# ProDoc.net
KiCad netlist of a schematic drawn in EasyEDA Pro
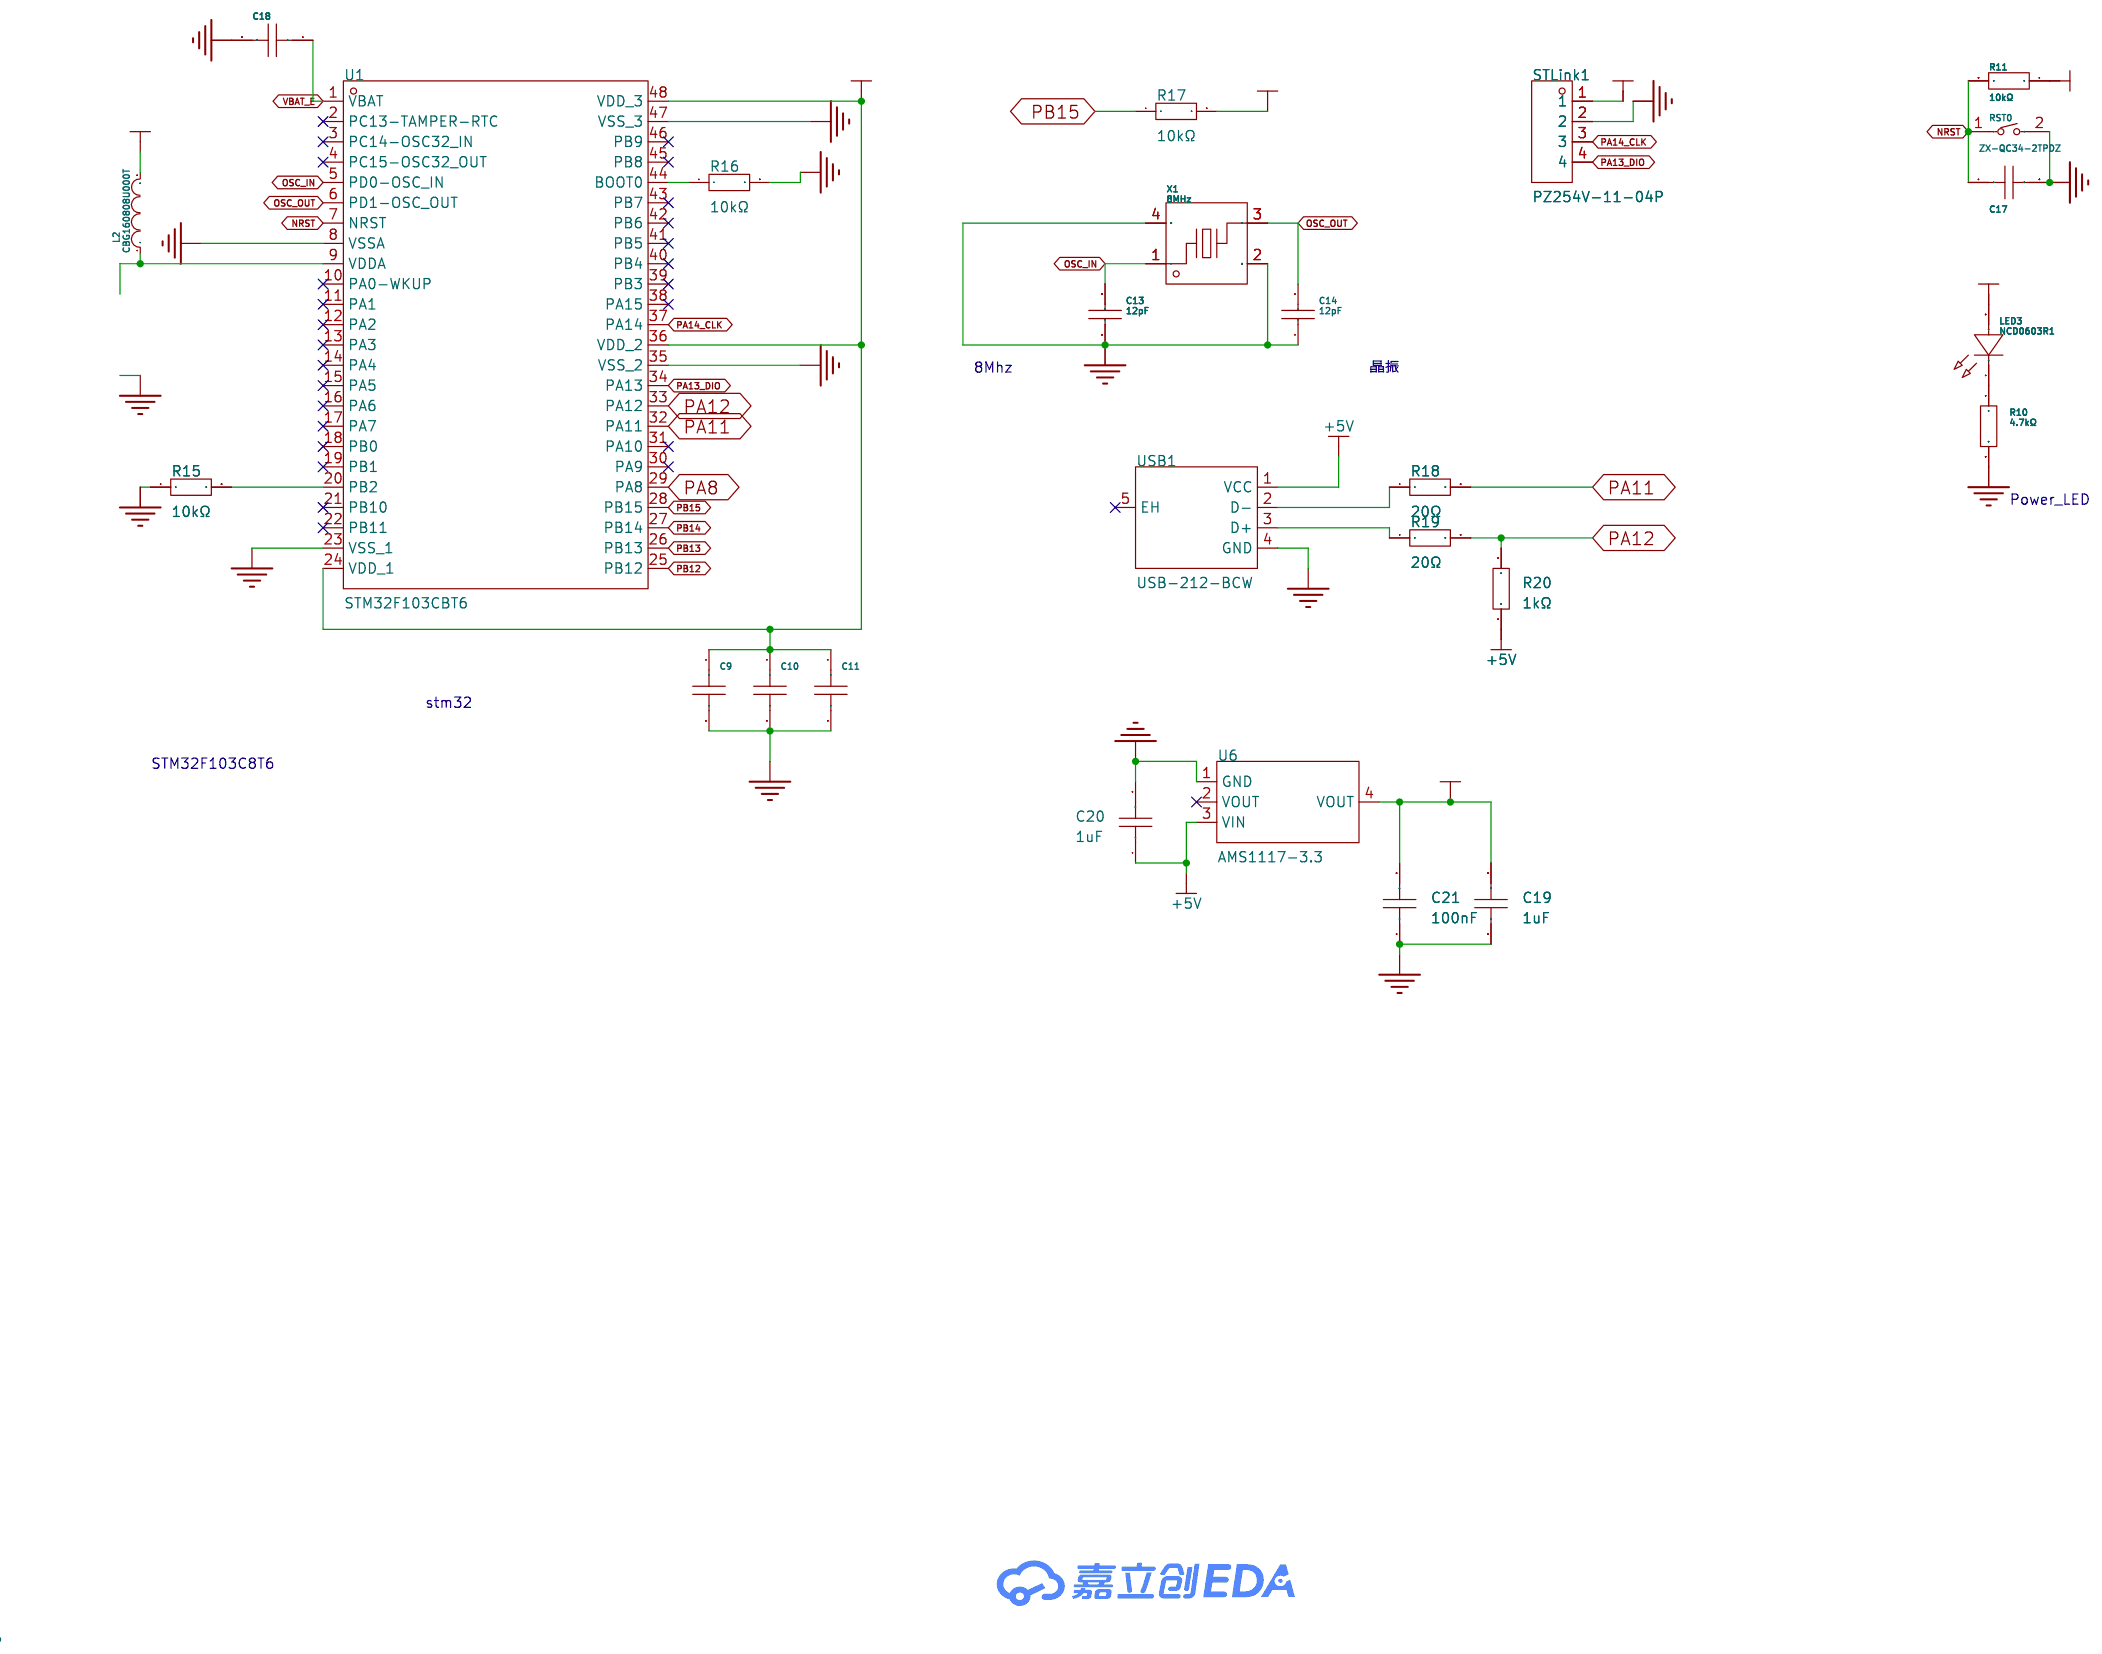
[diagram p0: P1]
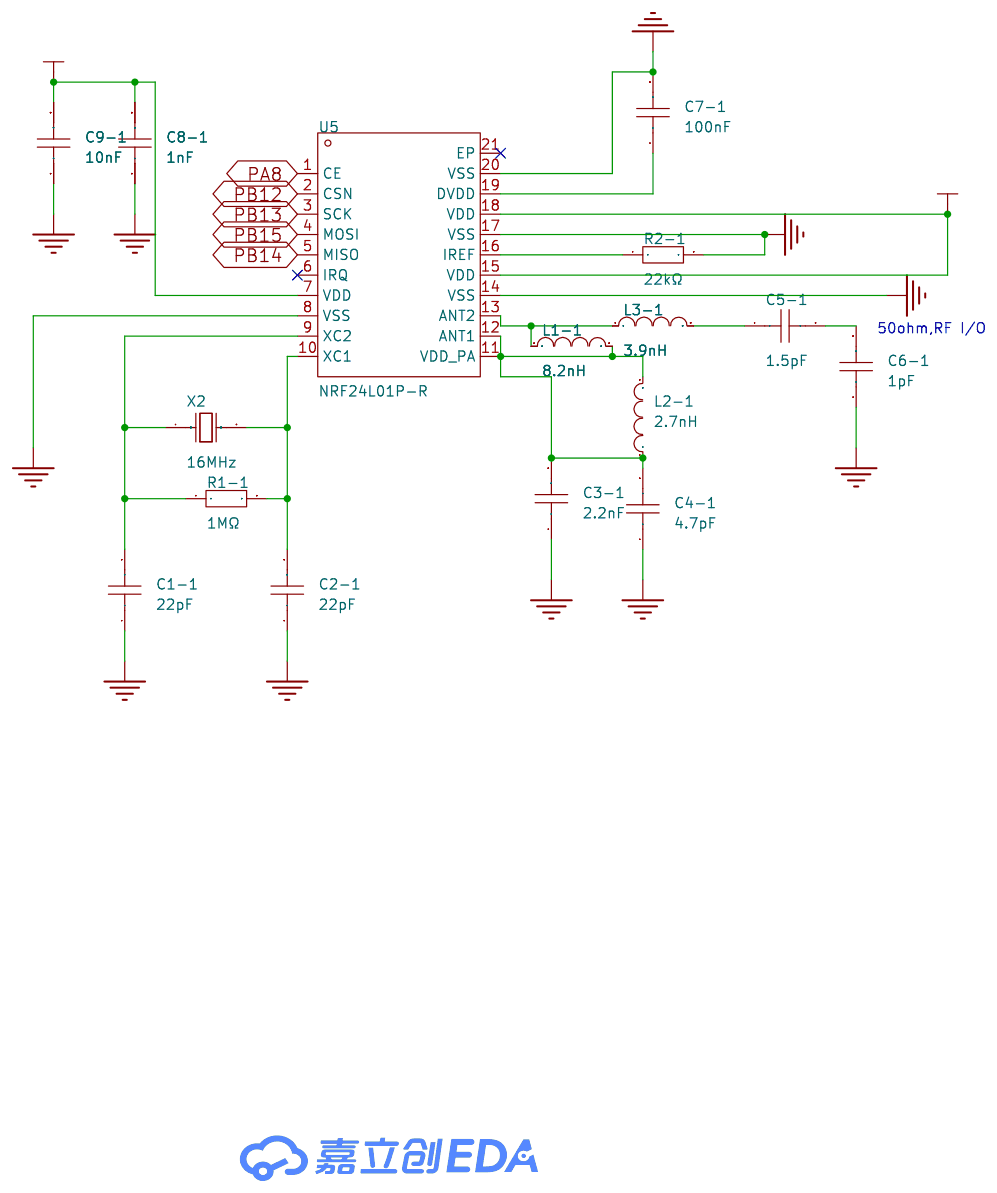
[diagram p1: P2]

(export (version "E")
  (design (tool "Eeschema 10.0.6"))
  (components
    (comp (ref "C9")
      (value "100nF")
      (fields
        (field (name "Manufacturer Part") "CT41G-0603-2X1-50V-0.1μF-K(N)")
        (field (name "Manufacturer") "TORCH(火炬)")
      )
      (libsource (lib "easyedapro") (part "CC0603JRNPO9BN101"))
    )
    (comp (ref "C10")
      (value "100nF")
      (fields
        (field (name "Manufacturer Part") "CT41G-0603-2X1-50V-0.1μF-K(N)")
        (field (name "Manufacturer") "TORCH(火炬)")
      )
      (libsource (lib "easyedapro") (part "CC0603JRNPO9BN101"))
    )
    (comp (ref "C11")
      (value "100nF")
      (fields
        (field (name "Manufacturer Part") "CT41G-0603-2X1-50V-0.1μF-K(N)")
        (field (name "Manufacturer") "TORCH(火炬)")
      )
      (libsource (lib "easyedapro") (part "CC0603JRNPO9BN101"))
    )
    (comp (ref "C13")
      (value "12pF")
      (fields
        (field (name "Manufacturer Part") "CL10C120JB8NNNC")
        (field (name "Manufacturer") "SAMSUNG(三星)")
      )
      (libsource (lib "easyedapro") (part "CC0603JRNPO9BN200"))
    )
    (comp (ref "C14")
      (value "12pF")
      (fields
        (field (name "Manufacturer Part") "CL10C120JB8NNNC")
        (field (name "Manufacturer") "SAMSUNG(三星)")
      )
      (libsource (lib "easyedapro") (part "CC0603JRNPO9BN200"))
    )
    (comp (ref "C17")
      (value "100nF")
      (fields
        (field (name "Manufacturer Part") "CT41G-0603-2X1-50V-0.1μF-K(N)")
        (field (name "Manufacturer") "TORCH(火炬)")
      )
      (libsource (lib "easyedapro") (part "CC0603JRNPO9BN101"))
    )
    (comp (ref "C18")
      (value "100nF")
      (fields
        (field (name "Manufacturer Part") "CT41G-0603-2X1-50V-0.1μF-K(N)")
        (field (name "Manufacturer") "TORCH(火炬)")
      )
      (libsource (lib "easyedapro") (part "CC0603JRNPO9BN101"))
    )
    (comp (ref "C19")
      (value "1uF")
      (footprint "easyedapro:C0603")
      (description "容值:1uF;精度:±10%;额定电压:50V;温度系数:X5R;")
      (fields
        (field (name "Manufacturer Part") "CL10A105KB8NNNC")
        (field (name "Manufacturer") "SAMSUNG(三星)")
      )
      (libsource (lib "easyedapro") (part "CL10A105KB8NNNC"))
    )
    (comp (ref "C20")
      (value "1uF")
      (footprint "easyedapro:C0603")
      (description "容值:1uF;精度:±10%;额定电压:50V;温度系数:X5R;")
      (fields
        (field (name "Manufacturer Part") "CL10A105KB8NNNC")
        (field (name "Manufacturer") "SAMSUNG(三星)")
      )
      (libsource (lib "easyedapro") (part "CL10A105KB8NNNC"))
    )
    (comp (ref "C21")
      (value "100nF")
      (footprint "easyedapro:C0603")
      (description "容值:100nF;精度:±10%;额定电压:50V;温度系数:X7R;")
      (fields
        (field (name "Manufacturer Part") "CGA0603X7R104K500JT")
        (field (name "Manufacturer") "HRE(芯声)")
      )
      (libsource (lib "easyedapro") (part "CGA0603X7R104K500JT"))
    )
    (comp (ref "L2")
      (value "CBG160808U000T")
      (footprint "easyedapro:L0603")
      (description "标称阻抗@测试频率:0Ω@100MHz;直流电阻(RDC):100mΩ;")
      (fields (field (name "Manufacturer") "FH(风华)"))
      (libsource (lib "easyedapro") (part "CBG160808U000T"))
    )
    (comp (ref "LED3")
      (value "NCD0603R1")
      (fields (field (name "Manufacturer") "国星光电"))
      (libsource (lib "easyedapro") (part "XL-1608SURC-06"))
    )
    (comp (ref "R10")
      (value "4.7kΩ")
      (footprint "easyedapro:R0603")
      (description "电阻类型:厚膜电阻;阻值:10kΩ;精度:±1%;功率:100mW;最大工作电压:75V;温度系数:±100ppm/°C;")
      (fields
        (field (name "Manufacturer Part") "0603WAF4701T5E")
        (field (name "Manufacturer") "UNI-ROYAL(厚声)")
      )
      (libsource (lib "easyedapro") (part "0603WAF1002T5E"))
    )
    (comp (ref "R11")
      (value "10kΩ")
      (footprint "easyedapro:R0603")
      (description "电阻类型:厚膜电阻;阻值:10kΩ;精度:±1%;功率:100mW;工作电压:75V;温度系数:±100ppm/℃;")
      (fields
        (field (name "Manufacturer Part") "0603WAF1002T5E")
        (field (name "Manufacturer") "UNI-ROYAL(厚声)")
      )
      (libsource (lib "easyedapro") (part "0603WAF1002T5E"))
    )
    (comp (ref "R15")
      (value "10kΩ")
      (description "电阻类型:厚膜电阻;阻值:10kΩ;精度:±1%;功率:100mW;工作电压:75V;温度系数:±100ppm/℃;")
      (fields
        (field (name "Manufacturer Part") "0603WAF1002T5E")
        (field (name "Manufacturer") "UNI-ROYAL(厚声)")
      )
      (libsource (lib "easyedapro") (part "电阻"))
    )
    (comp (ref "R16")
      (value "10kΩ")
      (description "电阻类型:厚膜电阻;阻值:10kΩ;精度:±1%;功率:100mW;工作电压:75V;温度系数:±100ppm/℃;")
      (fields
        (field (name "Manufacturer Part") "0603WAF1002T5E")
        (field (name "Manufacturer") "UNI-ROYAL(厚声)")
      )
      (libsource (lib "easyedapro") (part "电阻"))
    )
    (comp (ref "R17")
      (value "10kΩ")
      (description "电阻类型:厚膜电阻;阻值:10kΩ;精度:±1%;功率:100mW;工作电压:75V;温度系数:±100ppm/℃;")
      (fields
        (field (name "Manufacturer Part") "0603WAF1002T5E")
        (field (name "Manufacturer") "UNI-ROYAL(厚声)")
      )
      (libsource (lib "easyedapro") (part "电阻"))
    )
    (comp (ref "R18")
      (value "20Ω")
      (footprint "easyedapro:R0603")
      (description "电阻类型:厚膜电阻;阻值:20Ω;精度:±1%;功率:100mW;最大工作电压:75V;温度系数:±100ppm/°C;")
      (fields
        (field (name "Manufacturer Part") "0603WAF200JT5E")
        (field (name "Manufacturer") "UNI-ROYAL(厚声)")
      )
      (libsource (lib "easyedapro") (part "0603WAF200JT5E"))
    )
    (comp (ref "R19")
      (value "20Ω")
      (footprint "easyedapro:R0603")
      (description "电阻类型:厚膜电阻;阻值:20Ω;精度:±1%;功率:100mW;最大工作电压:75V;温度系数:±100ppm/°C;")
      (fields
        (field (name "Manufacturer Part") "0603WAF200JT5E")
        (field (name "Manufacturer") "UNI-ROYAL(厚声)")
      )
      (libsource (lib "easyedapro") (part "0603WAF200JT5E"))
    )
    (comp (ref "R20")
      (value "1kΩ")
      (footprint "easyedapro:R0603")
      (description "电阻类型:厚膜电阻;阻值:1kΩ;精度:±1%;功率:100mW;最大工作电压:75V;温度系数:±100ppm/°C;")
      (fields
        (field (name "Manufacturer Part") "0603WAF1001T5E")
        (field (name "Manufacturer") "UNI-ROYAL(厚声)")
      )
      (libsource (lib "easyedapro") (part "0603WAF1001T5E"))
    )
    (comp (ref "RST0")
      (value "ZX-QC34-2TPDZ")
      (footprint "easyedapro:KEY-SMD_L3.9-W3.0-LS5.0-EH")
      (fields (field (name "Manufacturer") "Megastar(兆星)"))
      (libsource (lib "easyedapro") (part "ZX-QC34-2TPDZ"))
    )
    (comp (ref "STLink1")
      (value "PZ254V-11-04P")
      (footprint "easyedapro:HDR-TH_4P-P2.54-V-M")
      (fields (field (name "Manufacturer") "XFCN(兴飞)"))
      (libsource (lib "easyedapro") (part "PZ254V-11-04P_C2691448"))
    )
    (comp (ref "U1")
      (value "STM32F103CBT6")
      (fields (field (name "Manufacturer") "ST(意法半导体)"))
      (libsource (lib "easyedapro") (part "APM32F103CBT6"))
    )
    (comp (ref "U6")
      (value "AMS1117-3.3")
      (footprint "easyedapro:SOT-223-3_L6.5-W3.4-P2.30-LS7.0-BR")
      (description "输出类型:固定;工作电压:16V;输出电压:3.3V;输出电流:1A;电源纹波抑制比(PSRR):72dB@(120Hz);输出极性:正极;")
      (fields (field (name "Manufacturer") "AMS"))
      (libsource (lib "easyedapro") (part "AMS1117-3.3"))
    )
    (comp (ref "USB1")
      (value "USB-212-BCW")
      (footprint "easyedapro:USB-A-SMD_USB-212-BCW")
      (description "连接器类型:Type-A;协议标准:USB 2.0;公母:公;安装方式:卧贴;触点数量:4P;端口数量:1;额定电流 - 电源:1.5A;工作温度:-20°C~+70°C;")
      (fields (field (name "Manufacturer") "XUNPU(讯普)"))
      (libsource (lib "easyedapro") (part "USB-212-BCW"))
    )
    (comp (ref "X1")
      (value "8MHz")
      (fields (field (name "Manufacturer Part") "X32258MOB4SI") (field (name "Manufacturer") "YXC(扬兴晶振)"))
      (libsource (lib "easyedapro") (part "X32258MOB4SI"))
    )
    (comp (ref "C1-1")
      (value "22pF")
      (fields
        (field (name "Manufacturer Part") "CL10C220JB8NNNC")
        (field (name "Manufacturer") "SAMSUNG(三星)")
      )
      (libsource (lib "easyedapro") (part "Capacitance"))
    )
    (comp (ref "C2-1")
      (value "22pF")
      (fields
        (field (name "Manufacturer Part") "CL10C220JB8NNNC")
        (field (name "Manufacturer") "SAMSUNG(三星)")
      )
      (libsource (lib "easyedapro") (part "Capacitance"))
    )
    (comp (ref "C3-1")
      (value "2.2nF")
      (fields
        (field (name "Manufacturer Part") "FCC0603B222K500CT")
        (field (name "Manufacturer") "FOJAN(富捷)")
      )
      (libsource (lib "easyedapro") (part "Capacitance"))
    )
    (comp (ref "C4-1")
      (value "4.7pF")
      (fields (field (name "Manufacturer Part") "0603CG4R7C500NT") (field (name "Manufacturer") "FH(风华)"))
      (libsource (lib "easyedapro") (part "Capacitance"))
    )
    (comp (ref "C5-1")
      (value "1.5pF")
      (fields (field (name "Manufacturer Part") "0603CG1R5C500NT") (field (name "Manufacturer") "FH(风华)"))
      (libsource (lib "easyedapro") (part "Capacitance"))
    )
    (comp (ref "C6-1")
      (value "1pF")
      (fields (field (name "Manufacturer Part") "0603CG1R0C500NT") (field (name "Manufacturer") "FH(风华)"))
      (libsource (lib "easyedapro") (part "Capacitance"))
    )
    (comp (ref "C7-1")
      (value "100nF")
      (fields
        (field (name "Manufacturer Part") "CGA0603X7R104K500JT")
        (field (name "Manufacturer") "HRE(芯声)")
      )
      (libsource (lib "easyedapro") (part "Capacitance"))
    )
    (comp (ref "C8-1")
      (value "1nF")
      (fields
        (field (name "Manufacturer Part") "CL10B102KB8NNNC")
        (field (name "Manufacturer") "SAMSUNG(三星)")
      )
      (libsource (lib "easyedapro") (part "Capacitance"))
    )
    (comp (ref "C9-1")
      (value "10nF")
      (fields (field (name "Manufacturer Part") "0603B103K500NT") (field (name "Manufacturer") "FH(风华)"))
      (libsource (lib "easyedapro") (part "Capacitance"))
    )
    (comp (ref "L1-1")
      (value "8.2nH")
      (fields (field (name "Manufacturer Part") "LQG18HN8N2J00D") (field (name "Manufacturer") "muRata(村田)"))
      (libsource (lib "easyedapro") (part "SDFL1608S100KTF"))
    )
    (comp (ref "L2-1")
      (value "2.7nH")
      (fields
        (field (name "Manufacturer Part") "SCC1608C2N7SSP")
        (field (name "Manufacturer") "Sunltech(顺磁)")
      )
      (libsource (lib "easyedapro") (part "SDFL1608S100KTF"))
    )
    (comp (ref "L3-1")
      (value "3.9nH")
      (fields
        (field (name "Manufacturer Part") "SDCL1608C3N9STDF")
        (field (name "Manufacturer") "Sunlord(顺络)")
      )
      (libsource (lib "easyedapro") (part "SDFL1608S100KTF"))
    )
    (comp (ref "R1-1")
      (value "1MΩ")
      (fields
        (field (name "Manufacturer Part") "0603WAF1004T5E")
        (field (name "Manufacturer") "UNI-ROYAL(厚声)")
      )
      (libsource (lib "easyedapro") (part "电阻"))
    )
    (comp (ref "R2-1")
      (value "22kΩ")
      (fields
        (field (name "Manufacturer Part") "0603WAF2202T5E")
        (field (name "Manufacturer") "UNI-ROYAL(厚声)")
      )
      (libsource (lib "easyedapro") (part "电阻"))
    )
    (comp (ref "U5")
      (value "NRF24L01P-R")
      (fields (field (name "Manufacturer") "NORDIC"))
      (libsource (lib "easyedapro") (part "NRF24L01_C1558392"))
    )
    (comp (ref "X2")
      (value "16MHz")
      (fields (field (name "Manufacturer Part") "X49SD16MSD2SC") (field (name "Manufacturer") "YXC(扬兴晶振)"))
      (libsource (lib "easyedapro") (part "SCBYS16X00000ELRJ"))
    )
  )
  (nets
    (net (code "1") (name "+5V") (class "Default")
      (node (ref "C20") (pin "1") (pinfunction "1_1") (pintype "unspecified"))
      (node (ref "R20") (pin "1") (pinfunction "1_1") (pintype "input"))
      (node (ref "U6") (pin "3") (pinfunction "VIN_3") (pintype "unspecified"))
      (node (ref "USB1") (pin "1") (pinfunction "VCC_1") (pintype "input"))
    )
    (net (code "2") (name "3V3") (class "Default")
      (node (ref "C10") (pin "1") (pinfunction "1_1") (pintype "unspecified"))
      (node (ref "C11") (pin "1") (pinfunction "1_1") (pintype "unspecified"))
      (node (ref "C19") (pin "2") (pinfunction "2_2") (pintype "unspecified"))
      (node (ref "C21") (pin "2") (pinfunction "2_2") (pintype "unspecified"))
      (node (ref "C8-1") (pin "2") (pinfunction "2_2") (pintype "input"))
      (node (ref "C9") (pin "1") (pinfunction "1_1") (pintype "unspecified"))
      (node (ref "C9-1") (pin "2") (pinfunction "2_2") (pintype "input"))
      (node (ref "L2") (pin "2") (pinfunction "2_2") (pintype "unspecified"))
      (node (ref "LED3") (pin "2") (pinfunction "A_2") (pintype "unspecified"))
      (node (ref "R11") (pin "1") (pinfunction "1_1") (pintype "input"))
      (node (ref "R17") (pin "2") (pinfunction "2_2") (pintype "input"))
      (node (ref "STLink1") (pin "1") (pinfunction "1_1") (pintype "unspecified"))
      (node (ref "U1") (pin "24") (pinfunction "VDD_1_24") (pintype "unspecified"))
      (node (ref "U1") (pin "36") (pinfunction "VDD_2_36") (pintype "unspecified"))
      (node (ref "U1") (pin "48") (pinfunction "VDD_3_48") (pintype "unspecified"))
      (node (ref "U5") (pin "15") (pinfunction "VDD_15") (pintype "unspecified"))
      (node (ref "U5") (pin "18") (pinfunction "VDD_18") (pintype "unspecified"))
      (node (ref "U5") (pin "7") (pinfunction "VDD_7") (pintype "unspecified"))
      (node (ref "U6") (pin "4") (pinfunction "VOUT_4") (pintype "unspecified"))
    )
    (net (code "3") (name "GND") (class "Default")
      (node (ref "C1-1") (pin "1") (pinfunction "1_1") (pintype "input"))
      (node (ref "C10") (pin "2") (pinfunction "2_2") (pintype "unspecified"))
      (node (ref "C11") (pin "2") (pinfunction "2_2") (pintype "unspecified"))
      (node (ref "C13") (pin "1") (pinfunction "1_1") (pintype "input"))
      (node (ref "C14") (pin "1") (pinfunction "1_1") (pintype "input"))
      (node (ref "C17") (pin "2") (pinfunction "2_2") (pintype "unspecified"))
      (node (ref "C18") (pin "2") (pinfunction "2_2") (pintype "unspecified"))
      (node (ref "C19") (pin "1") (pinfunction "1_1") (pintype "unspecified"))
      (node (ref "C2-1") (pin "1") (pinfunction "1_1") (pintype "input"))
      (node (ref "C20") (pin "2") (pinfunction "2_2") (pintype "unspecified"))
      (node (ref "C21") (pin "1") (pinfunction "1_1") (pintype "unspecified"))
      (node (ref "C3-1") (pin "1") (pinfunction "1_1") (pintype "input"))
      (node (ref "C4-1") (pin "1") (pinfunction "1_1") (pintype "input"))
      (node (ref "C6-1") (pin "1") (pinfunction "1_1") (pintype "input"))
      (node (ref "C7-1") (pin "2") (pinfunction "2_2") (pintype "input"))
      (node (ref "C8-1") (pin "1") (pinfunction "1_1") (pintype "input"))
      (node (ref "C9") (pin "2") (pinfunction "2_2") (pintype "unspecified"))
      (node (ref "C9-1") (pin "1") (pinfunction "1_1") (pintype "input"))
      (node (ref "R10") (pin "2") (pinfunction "2_2") (pintype "input"))
      (node (ref "R15") (pin "1") (pinfunction "1_1") (pintype "input"))
      (node (ref "R16") (pin "2") (pinfunction "2_2") (pintype "input"))
      (node (ref "R2-1") (pin "2") (pinfunction "2_2") (pintype "input"))
      (node (ref "RST0") (pin "2") (pinfunction "2_2") (pintype "unspecified"))
      (node (ref "STLink1") (pin "2") (pinfunction "2_2") (pintype "unspecified"))
      (node (ref "U1") (pin "23") (pinfunction "VSS_1_23") (pintype "unspecified"))
      (node (ref "U1") (pin "35") (pinfunction "VSS_2_35") (pintype "unspecified"))
      (node (ref "U1") (pin "47") (pinfunction "VSS_3_47") (pintype "unspecified"))
      (node (ref "U1") (pin "8") (pinfunction "VSSA_8") (pintype "unspecified"))
      (node (ref "U5") (pin "14") (pinfunction "VSS_14") (pintype "unspecified"))
      (node (ref "U5") (pin "17") (pinfunction "VSS_17") (pintype "unspecified"))
      (node (ref "U5") (pin "20") (pinfunction "VSS_20") (pintype "unspecified"))
      (node (ref "U5") (pin "8") (pinfunction "VSS_8") (pintype "unspecified"))
      (node (ref "U6") (pin "1") (pinfunction "GND_1") (pintype "unspecified"))
      (node (ref "USB1") (pin "4") (pinfunction "GND_4") (pintype "input"))
      (node (ref "X1") (pin "2") (pinfunction "GND_2") (pintype "input"))
      (node (ref "X1") (pin "4") (pinfunction "GND_4") (pintype "input"))
    )
    (net (code "4") (name "NRST") (class "Default")
      (node (ref "C17") (pin "1") (pinfunction "1_1") (pintype "unspecified"))
      (node (ref "R11") (pin "2") (pinfunction "2_2") (pintype "input"))
      (node (ref "RST0") (pin "1") (pinfunction "1_1") (pintype "unspecified"))
      (node (ref "U1") (pin "7") (pinfunction "NRST_7") (pintype "unspecified"))
    )
    (net (code "5") (name "Net-(C5-1-Pad1)") (class "Default")
      (node (ref "C5-1") (pin "1") (pinfunction "1_1") (pintype "input"))
      (node (ref "L3-1") (pin "2") (pinfunction "2_2") (pintype "unspecified"))
    )
    (net (code "6") (name "Net-(C5-1-Pad2)") (class "Default")
      (node (ref "C5-1") (pin "2") (pinfunction "2_2") (pintype "input"))
      (node (ref "C6-1") (pin "2") (pinfunction "2_2") (pintype "input"))
    )
    (net (code "7") (name "Net-(LED3-K)") (class "Default")
      (node (ref "LED3") (pin "1") (pinfunction "K_1") (pintype "unspecified"))
      (node (ref "R10") (pin "1") (pinfunction "1_1") (pintype "input"))
    )
    (net (code "8") (name "Net-(U1-BOOT0)") (class "Default")
      (node (ref "R16") (pin "1") (pinfunction "1_1") (pintype "input"))
      (node (ref "U1") (pin "44") (pinfunction "BOOT0_44") (pintype "unspecified"))
    )
    (net (code "9") (name "Net-(U1-PB2)") (class "Default")
      (node (ref "R15") (pin "2") (pinfunction "2_2") (pintype "input"))
      (node (ref "U1") (pin "20") (pinfunction "PB2_20") (pintype "unspecified"))
    )
    (net (code "10") (name "Net-(U1-VDDA)") (class "Default")
      (node (ref "L2") (pin "1") (pinfunction "1_1") (pintype "unspecified"))
      (node (ref "U1") (pin "9") (pinfunction "VDDA_9") (pintype "unspecified"))
    )
    (net (code "11") (name "Net-(U5-ANT1)") (class "Default")
      (node (ref "C3-1") (pin "2") (pinfunction "2_2") (pintype "input"))
      (node (ref "C4-1") (pin "2") (pinfunction "2_2") (pintype "input"))
      (node (ref "L1-1") (pin "2") (pinfunction "2_2") (pintype "unspecified"))
      (node (ref "L2-1") (pin "1") (pinfunction "1_1") (pintype "unspecified"))
      (node (ref "L2-1") (pin "2") (pinfunction "2_2") (pintype "unspecified"))
      (node (ref "U5") (pin "11") (pinfunction "VDD_PA_11") (pintype "unspecified"))
      (node (ref "U5") (pin "12") (pinfunction "ANT1_12") (pintype "unspecified"))
    )
    (net (code "12") (name "Net-(U5-ANT2)") (class "Default")
      (node (ref "L1-1") (pin "1") (pinfunction "1_1") (pintype "unspecified"))
      (node (ref "L3-1") (pin "1") (pinfunction "1_1") (pintype "unspecified"))
      (node (ref "U5") (pin "13") (pinfunction "ANT2_13") (pintype "unspecified"))
    )
    (net (code "13") (name "Net-(U5-DVDD)") (class "Default")
      (node (ref "C7-1") (pin "1") (pinfunction "1_1") (pintype "input"))
      (node (ref "U5") (pin "19") (pinfunction "DVDD_19") (pintype "unspecified"))
    )
    (net (code "14") (name "Net-(U5-IREF)") (class "Default")
      (node (ref "R2-1") (pin "1") (pinfunction "1_1") (pintype "input"))
      (node (ref "U5") (pin "16") (pinfunction "IREF_16") (pintype "unspecified"))
    )
    (net (code "15") (name "Net-(U5-XC1)") (class "Default")
      (node (ref "C2-1") (pin "2") (pinfunction "2_2") (pintype "input"))
      (node (ref "R1-1") (pin "2") (pinfunction "2_2") (pintype "input"))
      (node (ref "U5") (pin "10") (pinfunction "XC1_10") (pintype "unspecified"))
      (node (ref "X2") (pin "2") (pinfunction "OSC2_2") (pintype "input"))
    )
    (net (code "16") (name "Net-(U5-XC2)") (class "Default")
      (node (ref "C1-1") (pin "2") (pinfunction "2_2") (pintype "input"))
      (node (ref "R1-1") (pin "1") (pinfunction "1_1") (pintype "input"))
      (node (ref "U5") (pin "9") (pinfunction "XC2_9") (pintype "unspecified"))
      (node (ref "X2") (pin "1") (pinfunction "OSC1_1") (pintype "input"))
    )
    (net (code "17") (name "Net-(USB1-D+)") (class "Default")
      (node (ref "R19") (pin "1") (pinfunction "1_1") (pintype "input"))
      (node (ref "USB1") (pin "3") (pinfunction "D+_3") (pintype "input"))
    )
    (net (code "18") (name "Net-(USB1-D-)") (class "Default")
      (node (ref "R18") (pin "1") (pinfunction "1_1") (pintype "input"))
      (node (ref "USB1") (pin "2") (pinfunction "D-_2") (pintype "input"))
    )
    (net (code "19") (name "OSC_IN") (class "Default")
      (node (ref "C13") (pin "2") (pinfunction "2_2") (pintype "input"))
      (node (ref "U1") (pin "5") (pinfunction "PD0-OSC_IN_5") (pintype "unspecified"))
      (node (ref "X1") (pin "1") (pinfunction "1_1") (pintype "input"))
    )
    (net (code "20") (name "OSC_OUT") (class "Default")
      (node (ref "C14") (pin "2") (pinfunction "2_2") (pintype "input"))
      (node (ref "U1") (pin "6") (pinfunction "PD1-OSC_OUT_6") (pintype "unspecified"))
      (node (ref "X1") (pin "3") (pinfunction "3_3") (pintype "input"))
    )
    (net (code "21") (name "PA8") (class "Default")
      (node (ref "U1") (pin "29") (pinfunction "PA8_29") (pintype "unspecified"))
      (node (ref "U5") (pin "1") (pinfunction "CE_1") (pintype "unspecified"))
    )
    (net (code "22") (name "PA11") (class "Default")
      (node (ref "R18") (pin "2") (pinfunction "2_2") (pintype "input"))
      (node (ref "U1") (pin "32") (pinfunction "PA11_32") (pintype "unspecified"))
    )
    (net (code "23") (name "PA12") (class "Default")
      (node (ref "R19") (pin "2") (pinfunction "2_2") (pintype "input"))
      (node (ref "R20") (pin "2") (pinfunction "2_2") (pintype "input"))
      (node (ref "U1") (pin "33") (pinfunction "PA12_33") (pintype "unspecified"))
    )
    (net (code "24") (name "PA13_DIO") (class "Default")
      (node (ref "STLink1") (pin "4") (pinfunction "4_4") (pintype "unspecified"))
      (node (ref "U1") (pin "34") (pinfunction "PA13_34") (pintype "unspecified"))
    )
    (net (code "25") (name "PA14_CLK") (class "Default")
      (node (ref "STLink1") (pin "3") (pinfunction "3_3") (pintype "unspecified"))
      (node (ref "U1") (pin "37") (pinfunction "PA14_37") (pintype "unspecified"))
    )
    (net (code "26") (name "PB12") (class "Default")
      (node (ref "U1") (pin "25") (pinfunction "PB12_25") (pintype "unspecified"))
      (node (ref "U5") (pin "2") (pinfunction "CSN_2") (pintype "unspecified"))
    )
    (net (code "27") (name "PB13") (class "Default")
      (node (ref "U1") (pin "26") (pinfunction "PB13_26") (pintype "unspecified"))
      (node (ref "U5") (pin "3") (pinfunction "SCK_3") (pintype "unspecified"))
    )
    (net (code "28") (name "PB14") (class "Default")
      (node (ref "U1") (pin "27") (pinfunction "PB14_27") (pintype "unspecified"))
      (node (ref "U5") (pin "5") (pinfunction "MISO_5") (pintype "unspecified"))
    )
    (net (code "29") (name "PB15") (class "Default")
      (node (ref "R17") (pin "1") (pinfunction "1_1") (pintype "input"))
      (node (ref "U1") (pin "28") (pinfunction "PB15_28") (pintype "unspecified"))
      (node (ref "U5") (pin "4") (pinfunction "MOSI_4") (pintype "unspecified"))
    )
    (net (code "30") (name "VBAT_E") (class "Default")
      (node (ref "C18") (pin "1") (pinfunction "1_1") (pintype "unspecified"))
      (node (ref "U1") (pin "1") (pinfunction "VBAT_1") (pintype "unspecified"))
    )
    (net (code "31") (name "unconnected-(U1-PA0-WKUP-Pad10)") (class "Default")
      (node (ref "U1") (pin "10") (pinfunction "PA0-WKUP_10") (pintype "unspecified+no_connect"))
    )
    (net (code "32") (name "unconnected-(U1-PA1-Pad11)") (class "Default")
      (node (ref "U1") (pin "11") (pinfunction "PA1_11") (pintype "unspecified+no_connect"))
    )
    (net (code "33") (name "unconnected-(U1-PA2-Pad12)") (class "Default")
      (node (ref "U1") (pin "12") (pinfunction "PA2_12") (pintype "unspecified+no_connect"))
    )
    (net (code "34") (name "unconnected-(U1-PA3-Pad13)") (class "Default")
      (node (ref "U1") (pin "13") (pinfunction "PA3_13") (pintype "unspecified+no_connect"))
    )
    (net (code "35") (name "unconnected-(U1-PA4-Pad14)") (class "Default")
      (node (ref "U1") (pin "14") (pinfunction "PA4_14") (pintype "unspecified+no_connect"))
    )
    (net (code "36") (name "unconnected-(U1-PA5-Pad15)") (class "Default")
      (node (ref "U1") (pin "15") (pinfunction "PA5_15") (pintype "unspecified+no_connect"))
    )
    (net (code "37") (name "unconnected-(U1-PA6-Pad16)") (class "Default")
      (node (ref "U1") (pin "16") (pinfunction "PA6_16") (pintype "unspecified+no_connect"))
    )
    (net (code "38") (name "unconnected-(U1-PA7-Pad17)") (class "Default")
      (node (ref "U1") (pin "17") (pinfunction "PA7_17") (pintype "unspecified+no_connect"))
    )
    (net (code "39") (name "unconnected-(U1-PA9-Pad30)") (class "Default")
      (node (ref "U1") (pin "30") (pinfunction "PA9_30") (pintype "unspecified+no_connect"))
    )
    (net (code "40") (name "unconnected-(U1-PA10-Pad31)") (class "Default")
      (node (ref "U1") (pin "31") (pinfunction "PA10_31") (pintype "unspecified+no_connect"))
    )
    (net (code "41") (name "unconnected-(U1-PA15-Pad38)") (class "Default")
      (node (ref "U1") (pin "38") (pinfunction "PA15_38") (pintype "unspecified+no_connect"))
    )
    (net (code "42") (name "unconnected-(U1-PB0-Pad18)") (class "Default")
      (node (ref "U1") (pin "18") (pinfunction "PB0_18") (pintype "unspecified+no_connect"))
    )
    (net (code "43") (name "unconnected-(U1-PB1-Pad19)") (class "Default")
      (node (ref "U1") (pin "19") (pinfunction "PB1_19") (pintype "unspecified+no_connect"))
    )
    (net (code "44") (name "unconnected-(U1-PB3-Pad39)") (class "Default")
      (node (ref "U1") (pin "39") (pinfunction "PB3_39") (pintype "unspecified+no_connect"))
    )
    (net (code "45") (name "unconnected-(U1-PB4-Pad40)") (class "Default")
      (node (ref "U1") (pin "40") (pinfunction "PB4_40") (pintype "unspecified+no_connect"))
    )
    (net (code "46") (name "unconnected-(U1-PB5-Pad41)") (class "Default")
      (node (ref "U1") (pin "41") (pinfunction "PB5_41") (pintype "unspecified+no_connect"))
    )
    (net (code "47") (name "unconnected-(U1-PB6-Pad42)") (class "Default")
      (node (ref "U1") (pin "42") (pinfunction "PB6_42") (pintype "unspecified+no_connect"))
    )
    (net (code "48") (name "unconnected-(U1-PB7-Pad43)") (class "Default")
      (node (ref "U1") (pin "43") (pinfunction "PB7_43") (pintype "unspecified+no_connect"))
    )
    (net (code "49") (name "unconnected-(U1-PB8-Pad45)") (class "Default")
      (node (ref "U1") (pin "45") (pinfunction "PB8_45") (pintype "unspecified+no_connect"))
    )
    (net (code "50") (name "unconnected-(U1-PB9-Pad46)") (class "Default")
      (node (ref "U1") (pin "46") (pinfunction "PB9_46") (pintype "unspecified+no_connect"))
    )
    (net (code "51") (name "unconnected-(U1-PB10-Pad21)") (class "Default")
      (node (ref "U1") (pin "21") (pinfunction "PB10_21") (pintype "unspecified+no_connect"))
    )
    (net (code "52") (name "unconnected-(U1-PB11-Pad22)") (class "Default")
      (node (ref "U1") (pin "22") (pinfunction "PB11_22") (pintype "unspecified+no_connect"))
    )
    (net (code "53") (name "unconnected-(U1-PC13-TAMPER-RTC-Pad2)") (class "Default")
      (node (ref "U1") (pin "2") (pinfunction "PC13-TAMPER-RTC_2") (pintype "unspecified+no_connect"))
    )
    (net (code "54") (name "unconnected-(U1-PC14-OSC32_IN-Pad3)") (class "Default")
      (node (ref "U1") (pin "3") (pinfunction "PC14-OSC32_IN_3") (pintype "unspecified+no_connect"))
    )
    (net (code "55") (name "unconnected-(U1-PC15-OSC32_OUT-Pad4)") (class "Default")
      (node (ref "U1") (pin "4") (pinfunction "PC15-OSC32_OUT_4") (pintype "unspecified+no_connect"))
    )
    (net (code "56") (name "unconnected-(U5-EP-Pad21)") (class "Default")
      (node (ref "U5") (pin "21") (pinfunction "EP_21") (pintype "unspecified+no_connect"))
    )
    (net (code "57") (name "unconnected-(U5-IRQ-Pad6)") (class "Default")
      (node (ref "U5") (pin "6") (pinfunction "IRQ_6") (pintype "unspecified+no_connect"))
    )
    (net (code "58") (name "unconnected-(U6-VOUT-Pad2)") (class "Default")
      (node (ref "U6") (pin "2") (pinfunction "VOUT_2") (pintype "unspecified+no_connect"))
    )
    (net (code "59") (name "unconnected-(USB1-EH-Pad5)") (class "Default")
      (node (ref "USB1") (pin "5") (pinfunction "EH_5") (pintype "unspecified+no_connect"))
    )
  )
)
